# Tran_RF.net
KiCad netlist of a schematic drawn in Altium Designer
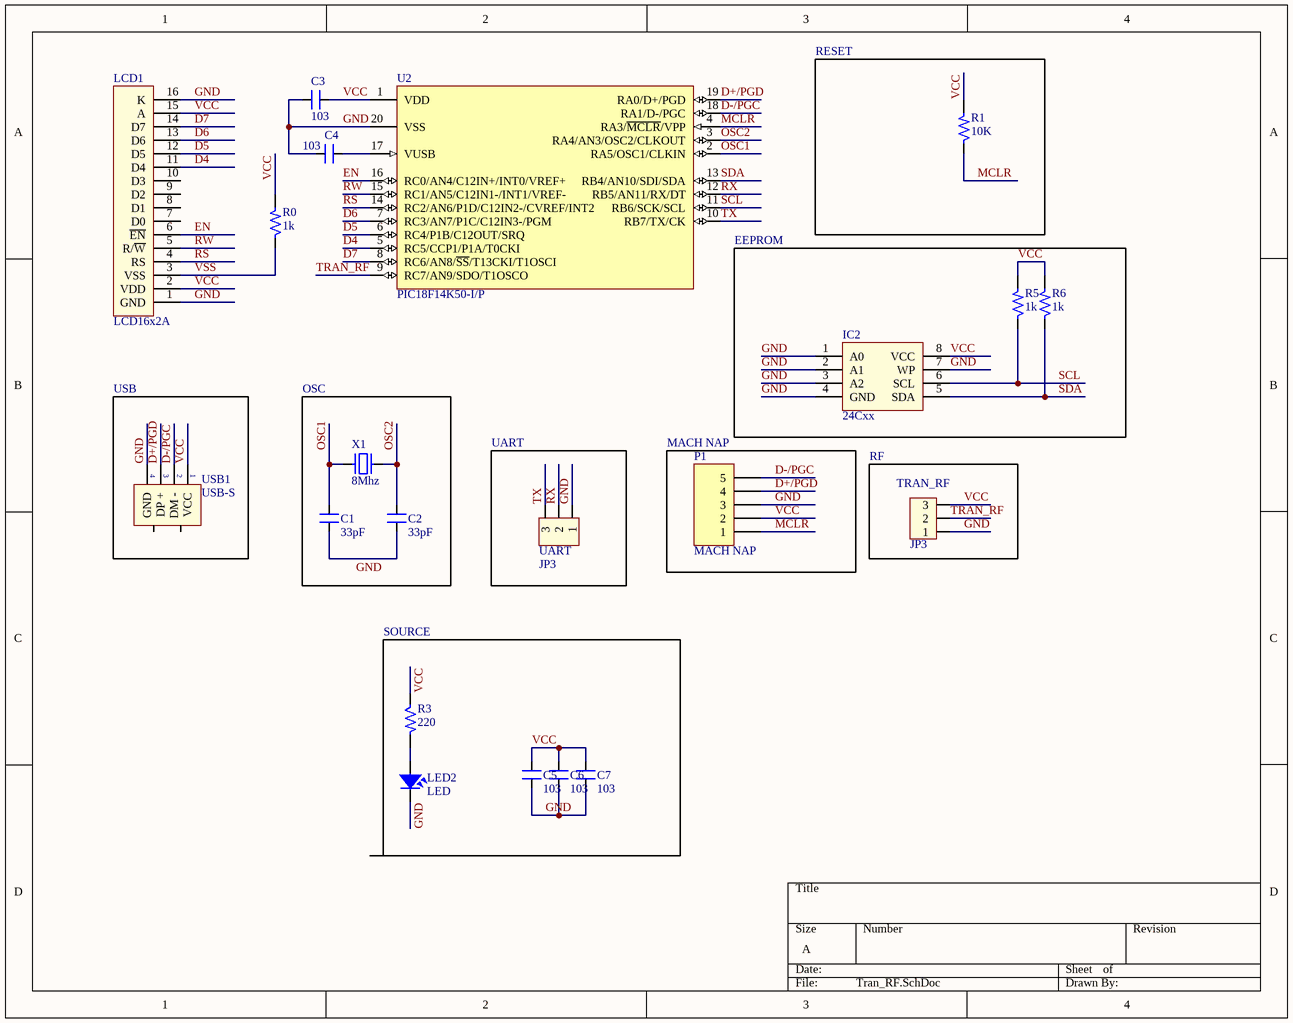
[diagram p0: Tran_RF.SchDoc]

(export (version "E")
  (design (tool "Eeschema 10.0.6"))
  (components
    (comp (ref "C1")
      (value "33pF")
      (footprint "SM-0805")
      (description "Cap SMD")
      (libsource (lib "syhaunguyen") (part "CM"))
    )
    (comp (ref "C2")
      (value "33pF")
      (footprint "SM-0805")
      (description "Cap SMD")
      (libsource (lib "syhaunguyen") (part "CM"))
    )
    (comp (ref "C3")
      (value "103")
      (footprint "SM-0805")
      (description "Cap SMD")
      (libsource (lib "syhaunguyen") (part "CM"))
    )
    (comp (ref "C4")
      (value "103")
      (footprint "SM-0805")
      (description "Cap SMD")
      (libsource (lib "syhaunguyen") (part "CM"))
    )
    (comp (ref "C5")
      (value "103")
      (footprint "SM-0805")
      (description "Cap SMD")
      (libsource (lib "syhaunguyen") (part "CM"))
    )
    (comp (ref "C6")
      (value "103")
      (footprint "SM-0805")
      (description "Cap SMD")
      (libsource (lib "syhaunguyen") (part "CM"))
    )
    (comp (ref "C7")
      (value "103")
      (footprint "SM-0805")
      (description "Cap SMD")
      (libsource (lib "syhaunguyen") (part "CM"))
    )
    (comp (ref "IC2")
      (value "24Cxx")
      (footprint "SO-G8")
      (description "Standard 2-Wire Bus Interface Serial EEPROM")
      (fields (field (name "COPYRIGHT BY") "VanDungEvn"))
      (libsource (lib "syhaunguyen") (part "24Cxx"))
    )
    (comp (ref "LCD1")
      (value "LCD16x2A")
      (footprint "LCD")
      (description "LCD dipslay 16 char, 2 line")
      (libsource (lib "syhaunguyen") (part "LCD16x2"))
    )
    (comp (ref "LED2")
      (value "LED")
      (footprint "Led-SMD")
      (description "LED Single colour Green and Red")
      (libsource (lib "syhaunguyen") (part "LED"))
    )
    (comp (ref "P1")
      (value "MACH NAP")
      (footprint "CON5")
      (description "Header, 5-Pin, Right Angle")
      (fields (field (name "PUBLISHER") "Altium Limited"))
      (libsource (lib "Miscellaneous Connectors") (part "Header 5H"))
    )
    (comp (ref "R0")
      (value "1k")
      (footprint "SM-1206")
      (description "Resistor 1/4W")
      (libsource (lib "syhaunguyen") (part "R"))
    )
    (comp (ref "R1")
      (value "10K")
      (footprint "SM-0805")
      (description "Resistor 1/4W")
      (libsource (lib "syhaunguyen") (part "R"))
    )
    (comp (ref "R3")
      (value "220")
      (footprint "SM-0805")
      (description "Resistor 1/4W")
      (libsource (lib "syhaunguyen") (part "R"))
    )
    (comp (ref "R5")
      (value "1k")
      (footprint "SM-0805")
      (description "Resistor 1/4W")
      (libsource (lib "syhaunguyen") (part "R"))
    )
    (comp (ref "R6")
      (value "1k")
      (footprint "SM-0805")
      (description "Resistor 1/4W")
      (libsource (lib "syhaunguyen") (part "R"))
    )
    (comp (ref "TRAN_RF")
      (value "JP3")
      (footprint "syhaunguyen:CON3")
      (description "Connector 3")
      (libsource (lib "syhaunguyen") (part "Con3"))
    )
    (comp (ref "U2")
      (value "PIC18F14K50-I/P")
      (footprint "SOP-20")
      (description "USB Flash Microcontroller with nanoWatt XLP Technology, 20-pin PDIP, Industrial Temperature")
      (fields (field (name "PUBLISHER") "Altium Limited"))
      (libsource (lib "Microchip Microcontroller 8-Bit PIC18") (part "PIC18F14K50-I/P"))
    )
    (comp (ref "UART")
      (value "JP3")
      (footprint "CON3")
      (description "Connector 3")
      (libsource (lib "") (part "Con3_1"))
    )
    (comp (ref "USB1")
      (value "USB-S")
      (footprint "USB-A-RA")
      (description "USB connector")
      (libsource (lib "syhaunguyen") (part "USB_S"))
    )
    (comp (ref "X1")
      (value "8Mhz")
      (footprint "XT2")
      (description "Crystal For all Crystal 2pin.")
      (libsource (lib "syhaunguyen") (part "XT2"))
    )
  )
  (nets
    (net (code "1") (name "/D+{slash}PGD") (class "Default")
      (node (ref "P1") (pin "4") (pinfunction "4_4") (pintype "passive"))
      (node (ref "U2") (pin "19") (pinfunction "RA0/D+/PGD_19") (pintype "bidirectional"))
      (node (ref "USB1") (pin "3") (pinfunction "DP_+_3") (pintype "passive"))
    )
    (net (code "2") (name "/D-{slash}PGC") (class "Default")
      (node (ref "P1") (pin "5") (pinfunction "5_5") (pintype "passive"))
      (node (ref "U2") (pin "18") (pinfunction "RA1/D-/PGC_18") (pintype "bidirectional"))
      (node (ref "USB1") (pin "2") (pinfunction "DM_-_2") (pintype "passive"))
    )
    (net (code "3") (name "/D4") (class "Default")
      (node (ref "LCD1") (pin "11") (pinfunction "D4_11") (pintype "passive"))
      (node (ref "U2") (pin "5") (pinfunction "RC5/CCP1/P1A/T0CKI_5") (pintype "bidirectional"))
    )
    (net (code "4") (name "/D5") (class "Default")
      (node (ref "LCD1") (pin "12") (pinfunction "D5_12") (pintype "passive"))
      (node (ref "U2") (pin "6") (pinfunction "RC4/P1B/C12OUT/SRQ_6") (pintype "bidirectional"))
    )
    (net (code "5") (name "/D6") (class "Default")
      (node (ref "LCD1") (pin "13") (pinfunction "D6_13") (pintype "passive"))
      (node (ref "U2") (pin "7") (pinfunction "RC3/AN7/P1C/C12IN3-/PGM_7") (pintype "bidirectional"))
    )
    (net (code "6") (name "/D7") (class "Default")
      (node (ref "LCD1") (pin "14") (pinfunction "D7_14") (pintype "passive"))
      (node (ref "U2") (pin "8") (pinfunction "RC6/AN8/~{SS}/T13CKI/T1OSCI_8") (pintype "bidirectional"))
    )
    (net (code "7") (name "/EN") (class "Default")
      (node (ref "LCD1") (pin "6") (pinfunction "~{EN}_6") (pintype "passive"))
      (node (ref "U2") (pin "16") (pinfunction "RC0/AN4/C12IN+/INT0/VREF+_16") (pintype "bidirectional"))
    )
    (net (code "8") (name "/GND") (class "Default")
      (node (ref "C1") (pin "1") (pinfunction "1_1") (pintype "passive"))
      (node (ref "C2") (pin "1") (pinfunction "1_1") (pintype "passive"))
      (node (ref "C3") (pin "1") (pinfunction "1_1") (pintype "passive"))
      (node (ref "C4") (pin "1") (pinfunction "1_1") (pintype "passive"))
      (node (ref "C5") (pin "1") (pinfunction "1_1") (pintype "passive"))
      (node (ref "C6") (pin "1") (pinfunction "1_1") (pintype "passive"))
      (node (ref "C7") (pin "1") (pinfunction "1_1") (pintype "passive"))
      (node (ref "IC2") (pin "1") (pinfunction "A0_1") (pintype "passive"))
      (node (ref "IC2") (pin "2") (pinfunction "A1_2") (pintype "passive"))
      (node (ref "IC2") (pin "3") (pinfunction "A2_3") (pintype "passive"))
      (node (ref "IC2") (pin "4") (pinfunction "GND_4") (pintype "power_in"))
      (node (ref "IC2") (pin "7") (pinfunction "WP_7") (pintype "passive"))
      (node (ref "LCD1") (pin "1") (pinfunction "GND_1") (pintype "passive"))
      (node (ref "LCD1") (pin "16") (pinfunction "K_16") (pintype "passive"))
      (node (ref "LED2") (pin "2") (pinfunction "2_2") (pintype "passive"))
      (node (ref "P1") (pin "3") (pinfunction "3_3") (pintype "passive"))
      (node (ref "TRAN_RF") (pin "1") (pinfunction "1_1") (pintype "passive"))
      (node (ref "U2") (pin "20") (pinfunction "VSS_20") (pintype "power_in"))
      (node (ref "UART") (pin "1") (pinfunction "1_1") (pintype "passive"))
      (node (ref "USB1") (pin "4") (pinfunction "GND_4") (pintype "passive"))
    )
    (net (code "9") (name "/MCLR") (class "Default")
      (node (ref "P1") (pin "1") (pinfunction "1_1") (pintype "passive"))
      (node (ref "R1") (pin "1") (pinfunction "1_1") (pintype "passive"))
      (node (ref "U2") (pin "4") (pinfunction "RA3/~{MCLR}/VPP_4") (pintype "input"))
    )
    (net (code "10") (name "/OSC1") (class "Default")
      (node (ref "C1") (pin "2") (pinfunction "2_2") (pintype "passive"))
      (node (ref "U2") (pin "2") (pinfunction "RA5/OSC1/CLKIN_2") (pintype "bidirectional"))
      (node (ref "X1") (pin "2") (pinfunction "2_2") (pintype "passive"))
    )
    (net (code "11") (name "/OSC2") (class "Default")
      (node (ref "C2") (pin "2") (pinfunction "2_2") (pintype "passive"))
      (node (ref "U2") (pin "3") (pinfunction "RA4/AN3/OSC2/CLKOUT_3") (pintype "bidirectional"))
      (node (ref "X1") (pin "1") (pinfunction "1_1") (pintype "passive"))
    )
    (net (code "12") (name "/RS") (class "Default")
      (node (ref "LCD1") (pin "4") (pinfunction "RS_4") (pintype "passive"))
      (node (ref "U2") (pin "14") (pinfunction "RC2/AN6/P1D/C12IN2-/CVREF/INT2_14") (pintype "bidirectional"))
    )
    (net (code "13") (name "/RW") (class "Default")
      (node (ref "LCD1") (pin "5") (pinfunction "R/~{W}_5") (pintype "passive"))
      (node (ref "U2") (pin "15") (pinfunction "RC1/AN5/C12IN1-/INT1/VREF-_15") (pintype "bidirectional"))
    )
    (net (code "14") (name "/RX") (class "Default")
      (node (ref "U2") (pin "12") (pinfunction "RB5/AN11/RX/DT_12") (pintype "bidirectional"))
      (node (ref "UART") (pin "2") (pinfunction "2_2") (pintype "passive"))
    )
    (net (code "15") (name "/SCL") (class "Default")
      (node (ref "IC2") (pin "6") (pinfunction "SCL_6") (pintype "passive"))
      (node (ref "R5") (pin "1") (pinfunction "1_1") (pintype "passive"))
      (node (ref "U2") (pin "11") (pinfunction "RB6/SCK/SCL_11") (pintype "bidirectional"))
    )
    (net (code "16") (name "/SDA") (class "Default")
      (node (ref "IC2") (pin "5") (pinfunction "SDA_5") (pintype "passive"))
      (node (ref "R6") (pin "1") (pinfunction "1_1") (pintype "passive"))
      (node (ref "U2") (pin "13") (pinfunction "RB4/AN10/SDI/SDA_13") (pintype "bidirectional"))
    )
    (net (code "17") (name "/TRAN_RF") (class "Default")
      (node (ref "TRAN_RF") (pin "2") (pinfunction "2_2") (pintype "passive"))
      (node (ref "U2") (pin "9") (pinfunction "RC7/AN9/SDO/T1OSCO_9") (pintype "bidirectional"))
    )
    (net (code "18") (name "/TX") (class "Default")
      (node (ref "U2") (pin "10") (pinfunction "RB7/TX/CK_10") (pintype "bidirectional"))
      (node (ref "UART") (pin "3") (pinfunction "3_3") (pintype "passive"))
    )
    (net (code "19") (name "/VCC") (class "Default")
      (node (ref "C3") (pin "2") (pinfunction "2_2") (pintype "passive"))
      (node (ref "C5") (pin "2") (pinfunction "2_2") (pintype "passive"))
      (node (ref "C6") (pin "2") (pinfunction "2_2") (pintype "passive"))
      (node (ref "C7") (pin "2") (pinfunction "2_2") (pintype "passive"))
      (node (ref "IC2") (pin "8") (pinfunction "VCC_8") (pintype "power_in"))
      (node (ref "LCD1") (pin "15") (pinfunction "A_15") (pintype "passive"))
      (node (ref "LCD1") (pin "2") (pinfunction "VDD_2") (pintype "passive"))
      (node (ref "P1") (pin "2") (pinfunction "2_2") (pintype "passive"))
      (node (ref "R0") (pin "2") (pinfunction "2_2") (pintype "passive"))
      (node (ref "R1") (pin "2") (pinfunction "2_2") (pintype "passive"))
      (node (ref "R3") (pin "1") (pinfunction "1_1") (pintype "passive"))
      (node (ref "R5") (pin "2") (pinfunction "2_2") (pintype "passive"))
      (node (ref "R6") (pin "2") (pinfunction "2_2") (pintype "passive"))
      (node (ref "TRAN_RF") (pin "3") (pinfunction "3_3") (pintype "passive"))
      (node (ref "U2") (pin "1") (pinfunction "VDD_1") (pintype "power_in"))
      (node (ref "USB1") (pin "1") (pinfunction "VCC_1") (pintype "passive"))
    )
    (net (code "20") (name "/VSS") (class "Default")
      (node (ref "LCD1") (pin "3") (pinfunction "VSS_3") (pintype "passive"))
      (node (ref "R0") (pin "1") (pinfunction "1_1") (pintype "passive"))
    )
    (net (code "21") (name "Net-(LED2-Pad1)") (class "Default")
      (node (ref "LED2") (pin "1") (pinfunction "1_1") (pintype "passive"))
      (node (ref "R3") (pin "2") (pinfunction "2_2") (pintype "passive"))
    )
    (net (code "22") (name "Net-(U2-VUSB)") (class "Default")
      (node (ref "C4") (pin "2") (pinfunction "2_2") (pintype "passive"))
      (node (ref "U2") (pin "17") (pinfunction "VUSB_17") (pintype "input"))
    )
    (net (code "23") (name "unconnected-(LCD1-D0-Pad7)") (class "Default")
      (node (ref "LCD1") (pin "7") (pinfunction "D0_7") (pintype "passive"))
    )
    (net (code "24") (name "unconnected-(LCD1-D1-Pad8)") (class "Default")
      (node (ref "LCD1") (pin "8") (pinfunction "D1_8") (pintype "passive"))
    )
    (net (code "25") (name "unconnected-(LCD1-D2-Pad9)") (class "Default")
      (node (ref "LCD1") (pin "9") (pinfunction "D2_9") (pintype "passive"))
    )
    (net (code "26") (name "unconnected-(LCD1-D3-Pad10)") (class "Default")
      (node (ref "LCD1") (pin "10") (pinfunction "D3_10") (pintype "passive"))
    )
    (net (code "27") (name "unconnected-(USB1-Pad5)") (class "Default")
      (node (ref "USB1") (pin "5") (pinfunction "5_5") (pintype "passive"))
    )
    (net (code "28") (name "unconnected-(USB1-Pad6)") (class "Default")
      (node (ref "USB1") (pin "6") (pinfunction "6_6") (pintype "passive"))
    )
  )
)
